# Stereo_RDS_Encoder-Analog_Board.net
KiCad netlist of a schematic drawn in EAGLE
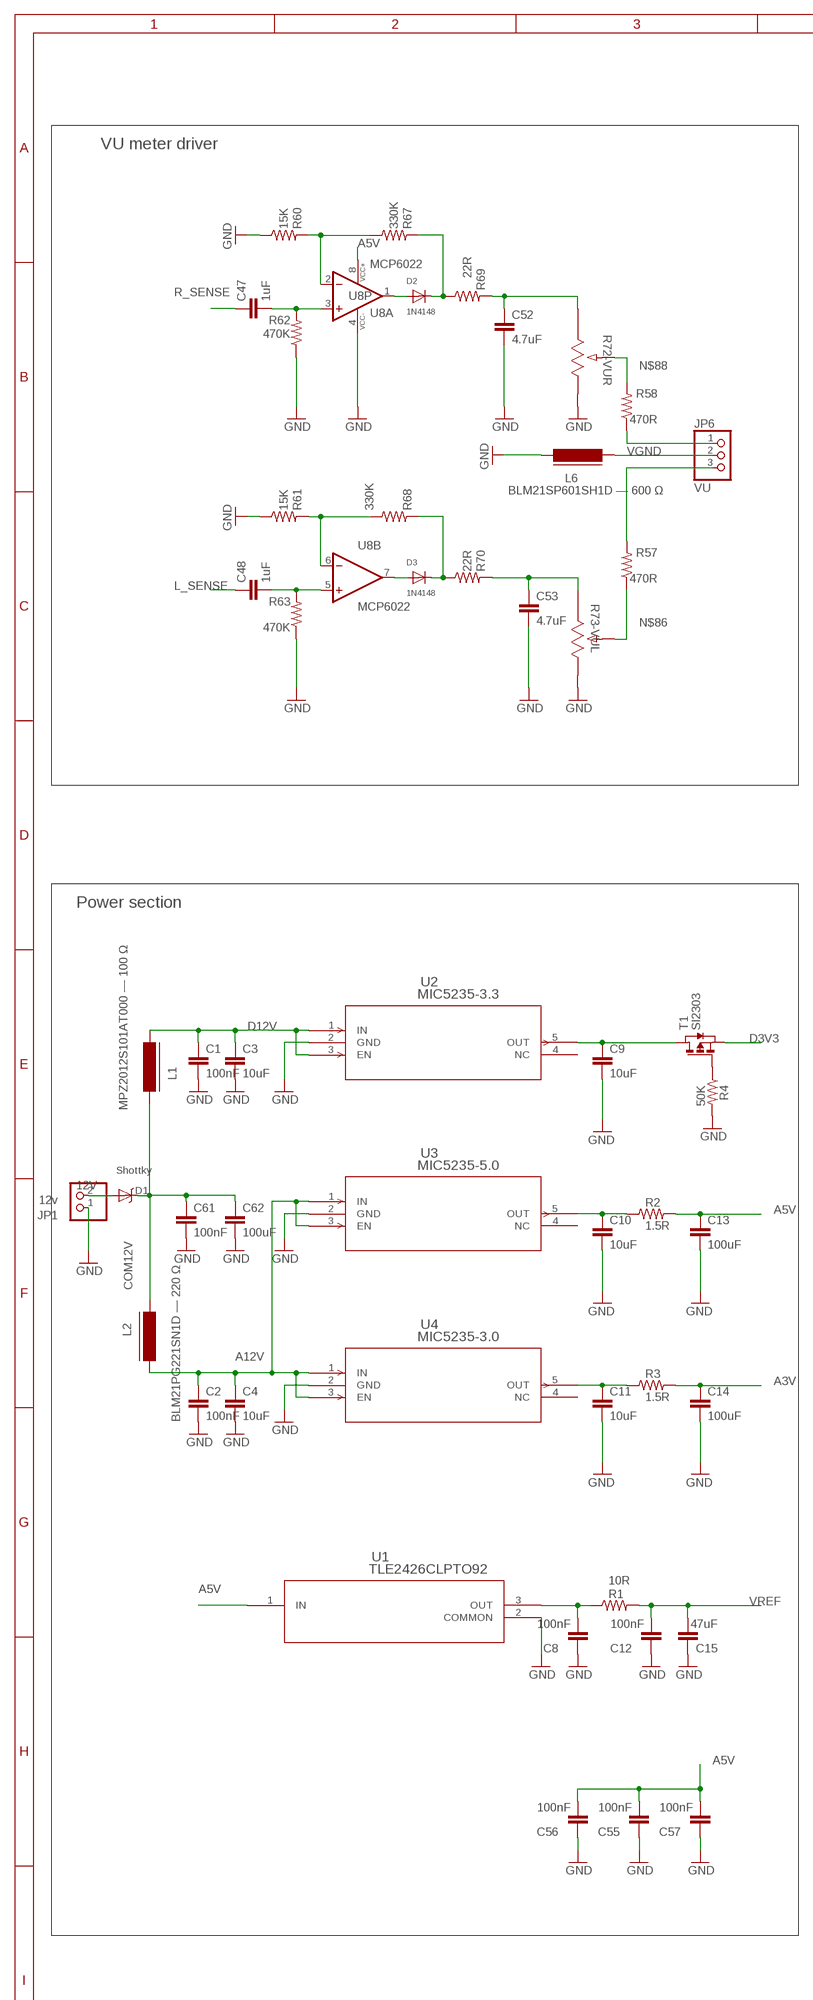
[diagram p0: schematic, sheet 1, part 1 of 2]
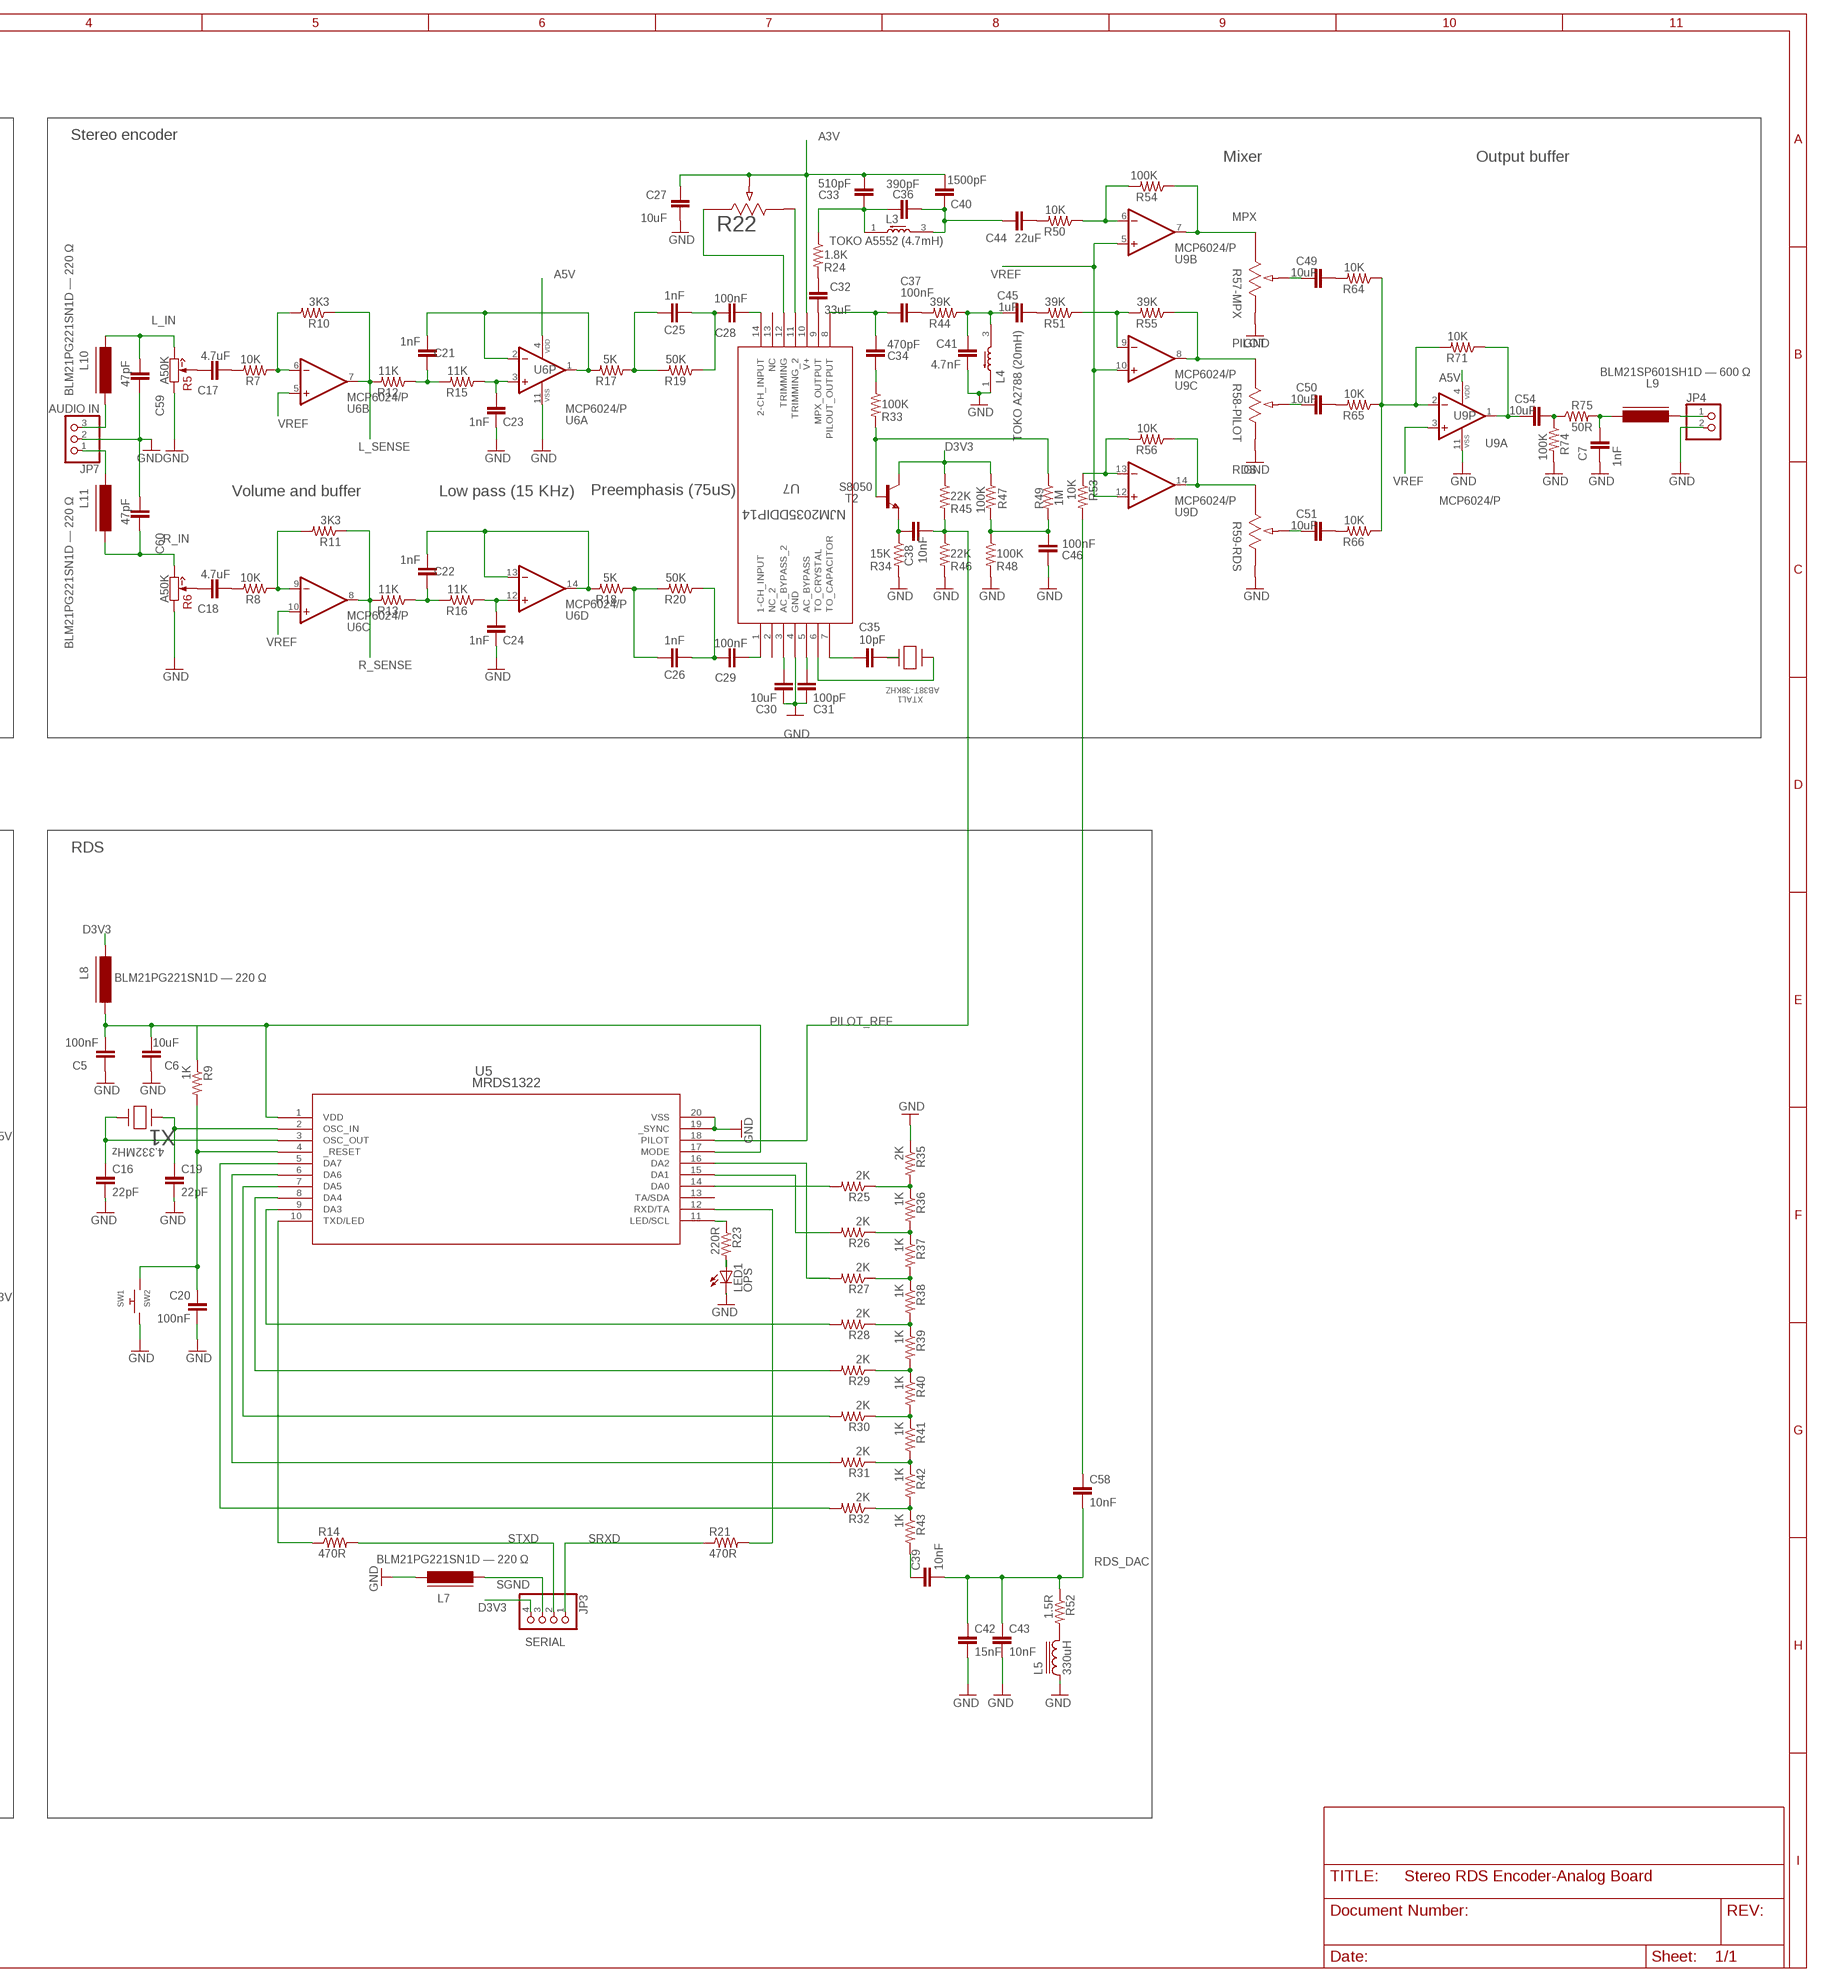
[diagram p1: schematic, sheet 1, part 2 of 2]

(export (version "E")
  (design (tool "Eeschema 10.0.6"))
  (components
    (comp (ref "C1")
      (value "100nF")
      (footprint "eagle-import:C0805")
      (libsource (lib "eagle-import") (part "C-EUC0805"))
    )
    (comp (ref "C2")
      (value "100nF")
      (footprint "eagle-import:C0805")
      (libsource (lib "eagle-import") (part "C-EUC0805"))
    )
    (comp (ref "C3")
      (value "10uF")
      (footprint "eagle-import:C0805")
      (libsource (lib "eagle-import") (part "C-EUC0805"))
    )
    (comp (ref "C4")
      (value "10uF")
      (footprint "eagle-import:C0805")
      (libsource (lib "eagle-import") (part "C-EUC0805"))
    )
    (comp (ref "C5")
      (value "100nF")
      (footprint "eagle-import:C0805")
      (libsource (lib "eagle-import") (part "C-EUC0805"))
    )
    (comp (ref "C6")
      (value "10uF")
      (footprint "eagle-import:C0805")
      (libsource (lib "eagle-import") (part "C-EUC0805"))
    )
    (comp (ref "C7")
      (value "1nF")
      (footprint "eagle-import:C0805")
      (libsource (lib "eagle-import") (part "C-EUC0805"))
    )
    (comp (ref "C8")
      (value "100nF")
      (footprint "eagle-import:C0805")
      (libsource (lib "eagle-import") (part "C-EUC0805"))
    )
    (comp (ref "C9")
      (value "10uF")
      (footprint "eagle-import:C0805")
      (libsource (lib "eagle-import") (part "C-EUC0805"))
    )
    (comp (ref "C10")
      (value "10uF")
      (footprint "eagle-import:C0805")
      (libsource (lib "eagle-import") (part "C-EUC0805"))
    )
    (comp (ref "C11")
      (value "10uF")
      (footprint "eagle-import:C0805")
      (libsource (lib "eagle-import") (part "C-EUC0805"))
    )
    (comp (ref "C12")
      (value "100nF")
      (footprint "eagle-import:C0805")
      (libsource (lib "eagle-import") (part "C-EUC0805"))
    )
    (comp (ref "C13")
      (value "100uF")
      (footprint "eagle-import:C0805")
      (libsource (lib "eagle-import") (part "C-EUC0805"))
    )
    (comp (ref "C14")
      (value "100uF")
      (footprint "eagle-import:C0805")
      (libsource (lib "eagle-import") (part "C-EUC0805"))
    )
    (comp (ref "C15")
      (value "47uF")
      (footprint "eagle-import:C0805")
      (libsource (lib "eagle-import") (part "C-EUC0805"))
    )
    (comp (ref "C16")
      (value "22pF")
      (footprint "eagle-import:C0805")
      (libsource (lib "eagle-import") (part "C-EUC0805"))
    )
    (comp (ref "C17")
      (value "4.7uF")
      (footprint "eagle-import:C0805")
      (libsource (lib "eagle-import") (part "C-EUC0805"))
    )
    (comp (ref "C18")
      (value "4.7uF")
      (footprint "eagle-import:C0805")
      (libsource (lib "eagle-import") (part "C-EUC0805"))
    )
    (comp (ref "C19")
      (value "22pF")
      (footprint "eagle-import:C0805")
      (libsource (lib "eagle-import") (part "C-EUC0805"))
    )
    (comp (ref "C20")
      (value "100nF")
      (footprint "eagle-import:C0805")
      (libsource (lib "eagle-import") (part "C-EUC0805"))
    )
    (comp (ref "C21")
      (value "1nF")
      (footprint "eagle-import:C0805")
      (libsource (lib "eagle-import") (part "C-EUC0805"))
    )
    (comp (ref "C22")
      (value "1nF")
      (footprint "eagle-import:C0805")
      (libsource (lib "eagle-import") (part "C-EUC0805"))
    )
    (comp (ref "C23")
      (value "1nF")
      (footprint "eagle-import:C0805")
      (libsource (lib "eagle-import") (part "C-EUC0805"))
    )
    (comp (ref "C24")
      (value "1nF")
      (footprint "eagle-import:C0805")
      (libsource (lib "eagle-import") (part "C-EUC0805"))
    )
    (comp (ref "C25")
      (value "1nF")
      (footprint "eagle-import:C0805")
      (libsource (lib "eagle-import") (part "C-EUC0805"))
    )
    (comp (ref "C26")
      (value "1nF")
      (footprint "eagle-import:C0805")
      (libsource (lib "eagle-import") (part "C-EUC0805"))
    )
    (comp (ref "C27")
      (value "10uF")
      (footprint "eagle-import:C0805")
      (libsource (lib "eagle-import") (part "C-EUC0805"))
    )
    (comp (ref "C28")
      (value "100nF")
      (footprint "eagle-import:C0805")
      (libsource (lib "eagle-import") (part "C-EUC0805"))
    )
    (comp (ref "C29")
      (value "100nF")
      (footprint "eagle-import:C0805")
      (libsource (lib "eagle-import") (part "C-EUC0805"))
    )
    (comp (ref "C30")
      (value "10uF")
      (footprint "eagle-import:C0805")
      (libsource (lib "eagle-import") (part "C-EUC0805"))
    )
    (comp (ref "C31")
      (value "100pF")
      (footprint "eagle-import:C0805")
      (libsource (lib "eagle-import") (part "C-EUC0805"))
    )
    (comp (ref "C32")
      (value "33uF")
      (footprint "eagle-import:C0805")
      (libsource (lib "eagle-import") (part "C-EUC0805"))
    )
    (comp (ref "C33")
      (value "510pF")
      (footprint "eagle-import:C0805")
      (libsource (lib "eagle-import") (part "C-EUC0805"))
    )
    (comp (ref "C34")
      (value "470pF")
      (footprint "eagle-import:C0805")
      (libsource (lib "eagle-import") (part "C-EUC0805"))
    )
    (comp (ref "C35")
      (value "10pF")
      (footprint "eagle-import:C0805")
      (libsource (lib "eagle-import") (part "C-EUC0805"))
    )
    (comp (ref "C36")
      (value "390pF")
      (footprint "eagle-import:C0805")
      (libsource (lib "eagle-import") (part "C-EUC0805"))
    )
    (comp (ref "C37")
      (value "100nF")
      (footprint "eagle-import:C0805")
      (libsource (lib "eagle-import") (part "C-EUC0805"))
    )
    (comp (ref "C38")
      (value "10nF")
      (footprint "eagle-import:C0805")
      (libsource (lib "eagle-import") (part "C-EUC0805"))
    )
    (comp (ref "C39")
      (value "10nF")
      (footprint "eagle-import:C0805")
      (libsource (lib "eagle-import") (part "C-EUC0805"))
    )
    (comp (ref "C40")
      (value "1500pF")
      (footprint "eagle-import:C0805")
      (libsource (lib "eagle-import") (part "C-EUC0805"))
    )
    (comp (ref "C41")
      (value "4.7nF")
      (footprint "eagle-import:C0805")
      (libsource (lib "eagle-import") (part "C-EUC0805"))
    )
    (comp (ref "C42")
      (value "15nF")
      (footprint "eagle-import:C0805")
      (libsource (lib "eagle-import") (part "C-EUC0805"))
    )
    (comp (ref "C43")
      (value "10nF")
      (footprint "eagle-import:C0805")
      (libsource (lib "eagle-import") (part "C-EUC0805"))
    )
    (comp (ref "C44")
      (value "22uF")
      (footprint "eagle-import:C0805")
      (libsource (lib "eagle-import") (part "C-EUC0805"))
    )
    (comp (ref "C45")
      (value "1uF")
      (footprint "eagle-import:C0805")
      (libsource (lib "eagle-import") (part "C-EUC0805"))
    )
    (comp (ref "C46")
      (value "100nF")
      (footprint "eagle-import:C0805")
      (libsource (lib "eagle-import") (part "C-EUC0805"))
    )
    (comp (ref "C47")
      (value "1uF")
      (footprint "eagle-import:C0805")
      (libsource (lib "eagle-import") (part "C-EUC0805"))
    )
    (comp (ref "C48")
      (value "1uF")
      (footprint "eagle-import:C0805")
      (libsource (lib "eagle-import") (part "C-EUC0805"))
    )
    (comp (ref "C49")
      (value "10uF")
      (footprint "eagle-import:C0805")
      (libsource (lib "eagle-import") (part "C-EUC0805"))
    )
    (comp (ref "C50")
      (value "10uF")
      (footprint "eagle-import:C0805")
      (libsource (lib "eagle-import") (part "C-EUC0805"))
    )
    (comp (ref "C51")
      (value "10uF")
      (footprint "eagle-import:C0805")
      (libsource (lib "eagle-import") (part "C-EUC0805"))
    )
    (comp (ref "C52")
      (value "4.7uF")
      (footprint "eagle-import:C0805")
      (libsource (lib "eagle-import") (part "C-EUC0805"))
    )
    (comp (ref "C53")
      (value "4.7uF")
      (footprint "eagle-import:C0805")
      (libsource (lib "eagle-import") (part "C-EUC0805"))
    )
    (comp (ref "C54")
      (value "10uF")
      (footprint "eagle-import:C0805")
      (libsource (lib "eagle-import") (part "C-EUC0805"))
    )
    (comp (ref "C55")
      (value "100nF")
      (footprint "eagle-import:C0805")
      (libsource (lib "eagle-import") (part "C-EUC0805"))
    )
    (comp (ref "C56")
      (value "100nF")
      (footprint "eagle-import:C0805")
      (libsource (lib "eagle-import") (part "C-EUC0805"))
    )
    (comp (ref "C57")
      (value "100nF")
      (footprint "eagle-import:C0805")
      (libsource (lib "eagle-import") (part "C-EUC0805"))
    )
    (comp (ref "C58")
      (value "10nF")
      (footprint "eagle-import:C0805")
      (libsource (lib "eagle-import") (part "C-EUC0805"))
    )
    (comp (ref "C59")
      (value "47pF")
      (footprint "eagle-import:C0805")
      (libsource (lib "eagle-import") (part "C-EUC0805"))
    )
    (comp (ref "C60")
      (value "47pF")
      (footprint "eagle-import:C0805")
      (libsource (lib "eagle-import") (part "C-EUC0805"))
    )
    (comp (ref "C61")
      (value "100nF")
      (footprint "eagle-import:C0805")
      (libsource (lib "eagle-import") (part "C-EUC0805"))
    )
    (comp (ref "C62")
      (value "100uF")
      (footprint "eagle-import:C0805")
      (libsource (lib "eagle-import") (part "C-EUC0805"))
    )
    (comp (ref "D1")
      (value "Shottky")
      (footprint "eagle-import:SMA-403D")
      (libsource (lib "eagle-import") (part "DIODE-SCHOTTKYSMA-403D"))
    )
    (comp (ref "D2")
      (value "1N4148")
      (footprint "eagle-import:SOD-323F")
      (libsource (lib "eagle-import") (part "DIODESOD-323F"))
    )
    (comp (ref "D3")
      (value "1N4148")
      (footprint "eagle-import:SOD-323F")
      (libsource (lib "eagle-import") (part "DIODESOD-323F"))
    )
    (comp (ref "JP1")
      (value "12v")
      (footprint "eagle-import:1X02")
      (libsource (lib "eagle-import") (part "PINHD-1X2"))
    )
    (comp (ref "JP3")
      (value "SERIAL")
      (footprint "eagle-import:1X04")
      (libsource (lib "eagle-import") (part "PINHD-1X4"))
    )
    (comp (ref "JP4")
      (value "PINHD-1X2")
      (footprint "eagle-import:1X02")
      (libsource (lib "eagle-import") (part "PINHD-1X2"))
    )
    (comp (ref "JP6")
      (value "VU")
      (footprint "eagle-import:1X03")
      (libsource (lib "eagle-import") (part "PINHD-1X3"))
    )
    (comp (ref "JP7")
      (value "AUDIO IN")
      (footprint "eagle-import:1X03")
      (libsource (lib "eagle-import") (part "PINHD-1X3"))
    )
    (comp (ref "L1")
      (value "MPZ2012S101AT000 — 100 Ω")
      (footprint "eagle-import:FB805")
      (libsource (lib "eagle-import") (part "FERRITE-0805"))
    )
    (comp (ref "L2")
      (value "BLM21PG221SN1D — 220 Ω")
      (footprint "eagle-import:FB805")
      (libsource (lib "eagle-import") (part "FERRITE-0805"))
    )
    (comp (ref "L3")
      (value "TOKO A5552 (4.7mH)")
      (footprint "eagle-import:7KMM")
      (libsource (lib "eagle-import") (part "7KMM"))
    )
    (comp (ref "L4")
      (value "TOKO A2788 (20mH)")
      (footprint "eagle-import:7KMM")
      (libsource (lib "eagle-import") (part "7KMM"))
    )
    (comp (ref "L5")
      (value "330uH")
      (footprint "eagle-import:8RB")
      (libsource (lib "eagle-import") (part "8RB"))
    )
    (comp (ref "L6")
      (value "BLM21SP601SH1D — 600 Ω")
      (footprint "eagle-import:FB805")
      (libsource (lib "eagle-import") (part "FERRITE-0805"))
    )
    (comp (ref "L7")
      (value "BLM21PG221SN1D — 220 Ω")
      (footprint "eagle-import:FB805")
      (libsource (lib "eagle-import") (part "FERRITE-0805"))
    )
    (comp (ref "L8")
      (value "BLM21PG221SN1D — 220 Ω")
      (footprint "eagle-import:FB805")
      (libsource (lib "eagle-import") (part "FERRITE-0805"))
    )
    (comp (ref "L9")
      (value "BLM21SP601SH1D — 600 Ω")
      (footprint "eagle-import:FB805")
      (libsource (lib "eagle-import") (part "FERRITE-0805"))
    )
    (comp (ref "L10")
      (value "BLM21PG221SN1D — 220 Ω")
      (footprint "eagle-import:FB805")
      (libsource (lib "eagle-import") (part "FERRITE-0805"))
    )
    (comp (ref "L11")
      (value "BLM21PG221SN1D — 220 Ω")
      (footprint "eagle-import:FB805")
      (libsource (lib "eagle-import") (part "FERRITE-0805"))
    )
    (comp (ref "LED1")
      (value "OPS")
      (footprint "eagle-import:CHIPLED_0805")
      (libsource (lib "eagle-import") (part "LEDCHIPLED_0805"))
    )
    (comp (ref "R1")
      (value "10R")
      (footprint "eagle-import:M0805")
      (libsource (lib "eagle-import") (part "R-US_M0805"))
    )
    (comp (ref "R2")
      (value "1.5R")
      (footprint "eagle-import:M0805")
      (libsource (lib "eagle-import") (part "R-US_M0805"))
    )
    (comp (ref "R3")
      (value "1.5R")
      (footprint "eagle-import:M0805")
      (libsource (lib "eagle-import") (part "R-US_M0805"))
    )
    (comp (ref "R4")
      (value "50K")
      (footprint "eagle-import:M0805")
      (libsource (lib "eagle-import") (part "R-US_M0805"))
    )
    (comp (ref "R5")
      (value "A50K")
      (footprint "eagle-import:RV09-SINGLE")
      (libsource (lib "eagle-import") (part "?A10K(9MM)"))
    )
    (comp (ref "R6")
      (value "A50K")
      (footprint "eagle-import:RV09-SINGLE")
      (libsource (lib "eagle-import") (part "?A10K(9MM)"))
    )
    (comp (ref "R7")
      (value "10K")
      (footprint "eagle-import:M0805")
      (libsource (lib "eagle-import") (part "R-US_M0805"))
    )
    (comp (ref "R8")
      (value "10K")
      (footprint "eagle-import:M0805")
      (libsource (lib "eagle-import") (part "R-US_M0805"))
    )
    (comp (ref "R9")
      (value "1K")
      (footprint "eagle-import:M0805")
      (libsource (lib "eagle-import") (part "R-US_M0805"))
    )
    (comp (ref "R10")
      (value "3K3")
      (footprint "eagle-import:M0805")
      (libsource (lib "eagle-import") (part "R-US_M0805"))
    )
    (comp (ref "R11")
      (value "3K3")
      (footprint "eagle-import:M0805")
      (libsource (lib "eagle-import") (part "R-US_M0805"))
    )
    (comp (ref "R12")
      (value "11K")
      (footprint "eagle-import:M0805")
      (libsource (lib "eagle-import") (part "R-US_M0805"))
    )
    (comp (ref "R13")
      (value "11K")
      (footprint "eagle-import:M0805")
      (libsource (lib "eagle-import") (part "R-US_M0805"))
    )
    (comp (ref "R14")
      (value "470R")
      (footprint "eagle-import:M0805")
      (libsource (lib "eagle-import") (part "R-US_M0805"))
    )
    (comp (ref "R15")
      (value "11K")
      (footprint "eagle-import:M0805")
      (libsource (lib "eagle-import") (part "R-US_M0805"))
    )
    (comp (ref "R16")
      (value "11K")
      (footprint "eagle-import:M0805")
      (libsource (lib "eagle-import") (part "R-US_M0805"))
    )
    (comp (ref "R17")
      (value "5K")
      (footprint "eagle-import:M0805")
      (libsource (lib "eagle-import") (part "R-US_M0805"))
    )
    (comp (ref "R18")
      (value "5K")
      (footprint "eagle-import:M0805")
      (libsource (lib "eagle-import") (part "R-US_M0805"))
    )
    (comp (ref "R19")
      (value "50K")
      (footprint "eagle-import:M0805")
      (libsource (lib "eagle-import") (part "R-US_M0805"))
    )
    (comp (ref "R20")
      (value "50K")
      (footprint "eagle-import:M0805")
      (libsource (lib "eagle-import") (part "R-US_M0805"))
    )
    (comp (ref "R21")
      (value "470R")
      (footprint "eagle-import:M0805")
      (libsource (lib "eagle-import") (part "R-US_M0805"))
    )
    (comp (ref "R22")
      (value "50K")
      (footprint "eagle-import:POT_3296W")
      (fields
        (field (name "MANUFACTURER_PART_NUMBER") "3296W-1-503LF")
        (field (name "COPYRIGHT") "Copyright (C) 2025 Ultra Librarian. All rights reserved.")
      )
      (libsource (lib "eagle-import") (part "3296W-1-503LF"))
    )
    (comp (ref "R23")
      (value "220R")
      (footprint "eagle-import:M0805")
      (libsource (lib "eagle-import") (part "R-US_M0805"))
    )
    (comp (ref "R24")
      (value "1.8K")
      (footprint "eagle-import:M0805")
      (libsource (lib "eagle-import") (part "R-US_M0805"))
    )
    (comp (ref "R25")
      (value "2K")
      (footprint "eagle-import:M0805")
      (libsource (lib "eagle-import") (part "R-US_M0805"))
    )
    (comp (ref "R26")
      (value "2K")
      (footprint "eagle-import:M0805")
      (libsource (lib "eagle-import") (part "R-US_M0805"))
    )
    (comp (ref "R27")
      (value "2K")
      (footprint "eagle-import:M0805")
      (libsource (lib "eagle-import") (part "R-US_M0805"))
    )
    (comp (ref "R28")
      (value "2K")
      (footprint "eagle-import:M0805")
      (libsource (lib "eagle-import") (part "R-US_M0805"))
    )
    (comp (ref "R29")
      (value "2K")
      (footprint "eagle-import:M0805")
      (libsource (lib "eagle-import") (part "R-US_M0805"))
    )
    (comp (ref "R30")
      (value "2K")
      (footprint "eagle-import:M0805")
      (libsource (lib "eagle-import") (part "R-US_M0805"))
    )
    (comp (ref "R31")
      (value "2K")
      (footprint "eagle-import:M0805")
      (libsource (lib "eagle-import") (part "R-US_M0805"))
    )
    (comp (ref "R32")
      (value "2K")
      (footprint "eagle-import:M0805")
      (libsource (lib "eagle-import") (part "R-US_M0805"))
    )
    (comp (ref "R33")
      (value "100K")
      (footprint "eagle-import:M0805")
      (libsource (lib "eagle-import") (part "R-US_M0805"))
    )
    (comp (ref "R34")
      (value "15K")
      (footprint "eagle-import:M0805")
      (libsource (lib "eagle-import") (part "R-US_M0805"))
    )
    (comp (ref "R35")
      (value "2K")
      (footprint "eagle-import:M0805")
      (libsource (lib "eagle-import") (part "R-US_M0805"))
    )
    (comp (ref "R36")
      (value "1K")
      (footprint "eagle-import:M0805")
      (libsource (lib "eagle-import") (part "R-US_M0805"))
    )
    (comp (ref "R37")
      (value "1K")
      (footprint "eagle-import:M0805")
      (libsource (lib "eagle-import") (part "R-US_M0805"))
    )
    (comp (ref "R38")
      (value "1K")
      (footprint "eagle-import:M0805")
      (libsource (lib "eagle-import") (part "R-US_M0805"))
    )
    (comp (ref "R39")
      (value "1K")
      (footprint "eagle-import:M0805")
      (libsource (lib "eagle-import") (part "R-US_M0805"))
    )
    (comp (ref "R40")
      (value "1K")
      (footprint "eagle-import:M0805")
      (libsource (lib "eagle-import") (part "R-US_M0805"))
    )
    (comp (ref "R41")
      (value "1K")
      (footprint "eagle-import:M0805")
      (libsource (lib "eagle-import") (part "R-US_M0805"))
    )
    (comp (ref "R42")
      (value "1K")
      (footprint "eagle-import:M0805")
      (libsource (lib "eagle-import") (part "R-US_M0805"))
    )
    (comp (ref "R43")
      (value "1K")
      (footprint "eagle-import:M0805")
      (libsource (lib "eagle-import") (part "R-US_M0805"))
    )
    (comp (ref "R44")
      (value "39K")
      (footprint "eagle-import:M0805")
      (libsource (lib "eagle-import") (part "R-US_M0805"))
    )
    (comp (ref "R45")
      (value "22K")
      (footprint "eagle-import:M0805")
      (libsource (lib "eagle-import") (part "R-US_M0805"))
    )
    (comp (ref "R46")
      (value "22K")
      (footprint "eagle-import:M0805")
      (libsource (lib "eagle-import") (part "R-US_M0805"))
    )
    (comp (ref "R47")
      (value "100K")
      (footprint "eagle-import:M0805")
      (libsource (lib "eagle-import") (part "R-US_M0805"))
    )
    (comp (ref "R48")
      (value "100K")
      (footprint "eagle-import:M0805")
      (libsource (lib "eagle-import") (part "R-US_M0805"))
    )
    (comp (ref "R49")
      (value "1M")
      (footprint "eagle-import:M0805")
      (libsource (lib "eagle-import") (part "R-US_M0805"))
    )
    (comp (ref "R50")
      (value "10K")
      (footprint "eagle-import:M0805")
      (libsource (lib "eagle-import") (part "R-US_M0805"))
    )
    (comp (ref "R51")
      (value "39K")
      (footprint "eagle-import:M0805")
      (libsource (lib "eagle-import") (part "R-US_M0805"))
    )
    (comp (ref "R52")
      (value "1.5R")
      (footprint "eagle-import:M0805")
      (libsource (lib "eagle-import") (part "R-US_M0805"))
    )
    (comp (ref "R53")
      (value "10K")
      (footprint "eagle-import:M0805")
      (libsource (lib "eagle-import") (part "R-US_M0805"))
    )
    (comp (ref "R54")
      (value "100K")
      (footprint "eagle-import:M0805")
      (libsource (lib "eagle-import") (part "R-US_M0805"))
    )
    (comp (ref "R55")
      (value "39K")
      (footprint "eagle-import:M0805")
      (libsource (lib "eagle-import") (part "R-US_M0805"))
    )
    (comp (ref "R56")
      (value "10K")
      (footprint "eagle-import:M0805")
      (libsource (lib "eagle-import") (part "R-US_M0805"))
    )
    (comp (ref "R57")
      (value "470R")
      (footprint "eagle-import:M0805")
      (libsource (lib "eagle-import") (part "R-US_M0805"))
    )
    (comp (ref "R57-MPX")
      (value "50K")
      (footprint "eagle-import:POT_3296W")
      (fields
        (field (name "MANUFACTURER_PART_NUMBER") "3296W-1-503LF")
        (field (name "COPYRIGHT") "Copyright (C) 2025 Ultra Librarian. All rights reserved.")
      )
      (libsource (lib "eagle-import") (part "3296W-1-503LF"))
    )
    (comp (ref "R58")
      (value "470R")
      (footprint "eagle-import:M0805")
      (libsource (lib "eagle-import") (part "R-US_M0805"))
    )
    (comp (ref "R58-PILOT")
      (value "50K")
      (footprint "eagle-import:POT_3296W")
      (fields
        (field (name "MANUFACTURER_PART_NUMBER") "3296W-1-503LF")
        (field (name "COPYRIGHT") "Copyright (C) 2025 Ultra Librarian. All rights reserved.")
      )
      (libsource (lib "eagle-import") (part "3296W-1-503LF"))
    )
    (comp (ref "R59-RDS")
      (value "50K")
      (footprint "eagle-import:POT_3296W")
      (fields
        (field (name "MANUFACTURER_PART_NUMBER") "3296W-1-503LF")
        (field (name "COPYRIGHT") "Copyright (C) 2025 Ultra Librarian. All rights reserved.")
      )
      (libsource (lib "eagle-import") (part "3296W-1-503LF"))
    )
    (comp (ref "R60")
      (value "15K")
      (footprint "eagle-import:M0805")
      (libsource (lib "eagle-import") (part "R-US_M0805"))
    )
    (comp (ref "R61")
      (value "15K")
      (footprint "eagle-import:M0805")
      (libsource (lib "eagle-import") (part "R-US_M0805"))
    )
    (comp (ref "R62")
      (value "470K")
      (footprint "eagle-import:M0805")
      (libsource (lib "eagle-import") (part "R-US_M0805"))
    )
    (comp (ref "R63")
      (value "470K")
      (footprint "eagle-import:M0805")
      (libsource (lib "eagle-import") (part "R-US_M0805"))
    )
    (comp (ref "R64")
      (value "10K")
      (footprint "eagle-import:M0805")
      (libsource (lib "eagle-import") (part "R-US_M0805"))
    )
    (comp (ref "R65")
      (value "10K")
      (footprint "eagle-import:M0805")
      (libsource (lib "eagle-import") (part "R-US_M0805"))
    )
    (comp (ref "R66")
      (value "10K")
      (footprint "eagle-import:M0805")
      (libsource (lib "eagle-import") (part "R-US_M0805"))
    )
    (comp (ref "R67")
      (value "330K")
      (footprint "eagle-import:M0805")
      (libsource (lib "eagle-import") (part "R-US_M0805"))
    )
    (comp (ref "R68")
      (value "330K")
      (footprint "eagle-import:M0805")
      (libsource (lib "eagle-import") (part "R-US_M0805"))
    )
    (comp (ref "R69")
      (value "22R")
      (footprint "eagle-import:M0805")
      (libsource (lib "eagle-import") (part "R-US_M0805"))
    )
    (comp (ref "R70")
      (value "22R")
      (footprint "eagle-import:M0805")
      (libsource (lib "eagle-import") (part "R-US_M0805"))
    )
    (comp (ref "R71")
      (value "10K")
      (footprint "eagle-import:M0805")
      (libsource (lib "eagle-import") (part "R-US_M0805"))
    )
    (comp (ref "R72-VUR")
      (value "50K")
      (footprint "eagle-import:POT_3296W")
      (fields
        (field (name "MANUFACTURER_PART_NUMBER") "3296W-1-503LF")
        (field (name "COPYRIGHT") "Copyright (C) 2025 Ultra Librarian. All rights reserved.")
      )
      (libsource (lib "eagle-import") (part "3296W-1-503LF"))
    )
    (comp (ref "R73-VUL")
      (value "50K")
      (footprint "eagle-import:POT_3296W")
      (fields
        (field (name "MANUFACTURER_PART_NUMBER") "3296W-1-503LF")
        (field (name "COPYRIGHT") "Copyright (C) 2025 Ultra Librarian. All rights reserved.")
      )
      (libsource (lib "eagle-import") (part "3296W-1-503LF"))
    )
    (comp (ref "R74")
      (value "100K")
      (footprint "eagle-import:M0805")
      (libsource (lib "eagle-import") (part "R-US_M0805"))
    )
    (comp (ref "R75")
      (value "50R")
      (footprint "eagle-import:M0805")
      (libsource (lib "eagle-import") (part "R-US_M0805"))
    )
    (comp (ref "SW1")
      (value "SW2")
      (footprint "eagle-import:BTN_CK_KSS")
      (libsource (lib "eagle-import") (part "SWITCH_PUSHBUTTONC&K_KSS"))
    )
    (comp (ref "T1")
      (value "SI2303")
      (footprint "eagle-import:SOT-23")
      (libsource (lib "eagle-import") (part "PMOSSOT23"))
    )
    (comp (ref "T2")
      (value "S8050")
      (footprint "eagle-import:SOT23")
      (libsource (lib "eagle-import") (part "BC846"))
    )
    (comp (ref "U1")
      (value "TLE2426CLPTO92")
      (footprint "eagle-import:TO92")
      (libsource (lib "eagle-import") (part "TLE2426CLPTO92"))
    )
    (comp (ref "U2")
      (value "MIC5235-3.3")
      (footprint "eagle-import:SOT-23-5_M5_MCH-M")
      (fields
        (field (name "MANUFACTURER_PART_NUMBER") "MIC5235-1.8YM5-TR")
        (field (name "COPYRIGHT") "Copyright (C) 2025 Ultra Librarian. All rights reserved.")
      )
      (libsource (lib "eagle-import") (part "MIC5235-1.8YM5-TRSOT-23-5_M5_MCH-M"))
    )
    (comp (ref "U3")
      (value "MIC5235-5.0")
      (footprint "eagle-import:SOT-23-5_M5_MCH-M")
      (fields
        (field (name "MANUFACTURER_PART_NUMBER") "MIC5235-1.8YM5-TR")
        (field (name "COPYRIGHT") "Copyright (C) 2025 Ultra Librarian. All rights reserved.")
      )
      (libsource (lib "eagle-import") (part "MIC5235-1.8YM5-TRSOT-23-5_M5_MCH-M"))
    )
    (comp (ref "U4")
      (value "MIC5235-3.0")
      (footprint "eagle-import:SOT-23-5_M5_MCH-M")
      (fields
        (field (name "MANUFACTURER_PART_NUMBER") "MIC5235-1.8YM5-TR")
        (field (name "COPYRIGHT") "Copyright (C) 2025 Ultra Librarian. All rights reserved.")
      )
      (libsource (lib "eagle-import") (part "MIC5235-1.8YM5-TRSOT-23-5_M5_MCH-M"))
    )
    (comp (ref "U5")
      (value "MRDS1322")
      (footprint "eagle-import:PDIP20_300MC_MCH")
      (fields
        (field (name "MANUFACTURER_PART_NUMBER") "PIC16F1509-E/P")
        (field (name "COPYRIGHT") "Copyright (C) 2025 Ultra Librarian. All rights reserved.")
      )
      (libsource (lib "eagle-import") (part "MRDS1322"))
    )
    (comp (ref "U6")
      (value "MCP6024/P")
      (footprint "eagle-import:DIL14")
      (libsource (lib "eagle-import") (part "MCP6024/P"))
    )
    (comp (ref "U7")
      (value "NJM2035DDIP14")
      (footprint "eagle-import:DIP14")
      (libsource (lib "eagle-import") (part "NJM2035DDIP14"))
    )
    (comp (ref "U8")
      (value "MCP6022")
      (footprint "eagle-import:DIL08")
      (libsource (lib "eagle-import") (part "TL072P"))
    )
    (comp (ref "U9")
      (value "MCP6024/P")
      (footprint "eagle-import:DIL14")
      (libsource (lib "eagle-import") (part "MCP6024/P"))
    )
    (comp (ref "X1")
      (value "4.332MHz")
      (footprint "eagle-import:XTAL_HC-49_U-S_CFC")
      (fields
        (field (name "MANUFACTURER_PART_NUMBER") "HC-49/U-S15000000ABJB")
        (field (name "COPYRIGHT") "Copyright (C) 2025 Ultra Librarian. All rights reserved.")
      )
      (libsource (lib "eagle-import") (part "HC-49/U-S15000000ABJB"))
    )
    (comp (ref "XTAL1")
      (value "AB38T-38KHZ")
      (footprint "eagle-import:XTAL_AB38T_ABR")
      (fields
        (field (name "MANUFACTURER_PART_NUMBER") "AB38T-32.768KHZ")
        (field (name "COPYRIGHT") "Copyright (C) 2025 Ultra Librarian. All rights reserved.")
      )
      (libsource (lib "eagle-import") (part "AB38T-32.768KHZ"))
    )
  )
  (nets
    (net (code "1") (name "/12V") (class "Default")
      (node (ref "D1") (pin "A") (pinfunction "A_A") (pintype "passive"))
      (node (ref "JP1") (pin "2") (pinfunction "2_2") (pintype "passive"))
    )
    (net (code "2") (name "/A3V") (class "Default")
      (node (ref "C14") (pin "1") (pinfunction "1_1") (pintype "passive"))
      (node (ref "C27") (pin "1") (pinfunction "1_1") (pintype "passive"))
      (node (ref "C33") (pin "1") (pinfunction "1_1") (pintype "passive"))
      (node (ref "C40") (pin "1") (pinfunction "1_1") (pintype "passive"))
      (node (ref "R22") (pin "2") (pinfunction "2_2") (pintype "passive"))
      (node (ref "R3") (pin "2") (pinfunction "2_2") (pintype "passive"))
      (node (ref "U7") (pin "10") (pinfunction "V+_10") (pintype "power_in"))
    )
    (net (code "3") (name "/A5V") (class "Default")
      (node (ref "C13") (pin "1") (pinfunction "1_1") (pintype "passive"))
      (node (ref "C55") (pin "2") (pinfunction "2_2") (pintype "passive"))
      (node (ref "C56") (pin "2") (pinfunction "2_2") (pintype "passive"))
      (node (ref "C57") (pin "2") (pinfunction "2_2") (pintype "passive"))
      (node (ref "R2") (pin "2") (pinfunction "2_2") (pintype "passive"))
      (node (ref "U1") (pin "1") (pinfunction "IN_1") (pintype "input"))
      (node (ref "U6") (pin "4") (pinfunction "VDD_4") (pintype "power_in"))
      (node (ref "U8") (pin "8") (pinfunction "VCC+_8") (pintype "power_in"))
      (node (ref "U9") (pin "4") (pinfunction "VDD_4") (pintype "power_in"))
    )
    (net (code "4") (name "/A12V") (class "Default")
      (node (ref "C2") (pin "1") (pinfunction "1_1") (pintype "passive"))
      (node (ref "C4") (pin "1") (pinfunction "1_1") (pintype "passive"))
      (node (ref "L2") (pin "2") (pinfunction "2_2") (pintype "passive"))
      (node (ref "U3") (pin "1") (pinfunction "IN_1") (pintype "input"))
      (node (ref "U3") (pin "3") (pinfunction "EN_3") (pintype "input"))
      (node (ref "U4") (pin "1") (pinfunction "IN_1") (pintype "input"))
      (node (ref "U4") (pin "3") (pinfunction "EN_3") (pintype "input"))
    )
    (net (code "5") (name "/COM12V") (class "Default")
      (node (ref "C61") (pin "1") (pinfunction "1_1") (pintype "passive"))
      (node (ref "C62") (pin "1") (pinfunction "1_1") (pintype "passive"))
      (node (ref "D1") (pin "C") (pinfunction "C_C") (pintype "passive"))
      (node (ref "L1") (pin "1") (pinfunction "1_1") (pintype "passive"))
      (node (ref "L2") (pin "1") (pinfunction "1_1") (pintype "passive"))
    )
    (net (code "6") (name "/D3V3") (class "Default")
      (node (ref "JP3") (pin "4") (pinfunction "4_4") (pintype "passive"))
      (node (ref "L8") (pin "1") (pinfunction "1_1") (pintype "passive"))
      (node (ref "R45") (pin "1") (pinfunction "1_1") (pintype "passive"))
      (node (ref "R47") (pin "1") (pinfunction "1_1") (pintype "passive"))
      (node (ref "T1") (pin "2") (pinfunction "S_2") (pintype "passive"))
      (node (ref "T2") (pin "3") (pinfunction "C_3") (pintype "passive"))
    )
    (net (code "7") (name "/D12V") (class "Default")
      (node (ref "C1") (pin "1") (pinfunction "1_1") (pintype "passive"))
      (node (ref "C3") (pin "1") (pinfunction "1_1") (pintype "passive"))
      (node (ref "L1") (pin "2") (pinfunction "2_2") (pintype "passive"))
      (node (ref "U2") (pin "1") (pinfunction "IN_1") (pintype "input"))
      (node (ref "U2") (pin "3") (pinfunction "EN_3") (pintype "input"))
    )
    (net (code "8") (name "/L_IN") (class "Default")
      (node (ref "C59") (pin "2") (pinfunction "2_2") (pintype "passive"))
      (node (ref "L10") (pin "1") (pinfunction "1_1") (pintype "passive"))
      (node (ref "R5") (pin "3") (pinfunction "CW_3") (pintype "passive"))
    )
    (net (code "9") (name "/L_SENSE") (class "Default")
      (node (ref "C48") (pin "1") (pinfunction "1_1") (pintype "passive"))
      (node (ref "R10") (pin "1") (pinfunction "1_1") (pintype "passive"))
      (node (ref "R12") (pin "2") (pinfunction "2_2") (pintype "passive"))
      (node (ref "U6") (pin "7") (pinfunction "OUT_7") (pintype "output"))
    )
    (net (code "10") (name "/MPX") (class "Default")
      (node (ref "R54") (pin "1") (pinfunction "1_1") (pintype "passive"))
      (node (ref "R57-MPX") (pin "1") (pinfunction "1_1") (pintype "passive"))
      (node (ref "U9") (pin "7") (pinfunction "OUT_7") (pintype "output"))
    )
    (net (code "11") (name "/N$86") (class "Default")
      (node (ref "R57") (pin "1") (pinfunction "1_1") (pintype "passive"))
      (node (ref "R73-VUL") (pin "2") (pinfunction "2_2") (pintype "passive"))
    )
    (net (code "12") (name "/N$88") (class "Default")
      (node (ref "R58") (pin "2") (pinfunction "2_2") (pintype "passive"))
      (node (ref "R72-VUR") (pin "2") (pinfunction "2_2") (pintype "passive"))
    )
    (net (code "13") (name "/PILOT") (class "Default")
      (node (ref "R55") (pin "1") (pinfunction "1_1") (pintype "passive"))
      (node (ref "R58-PILOT") (pin "1") (pinfunction "1_1") (pintype "passive"))
      (node (ref "U9") (pin "8") (pinfunction "OUT_8") (pintype "output"))
    )
    (net (code "14") (name "/PILOT_REF") (class "Default")
      (node (ref "C38") (pin "2") (pinfunction "2_2") (pintype "passive"))
      (node (ref "R45") (pin "2") (pinfunction "2_2") (pintype "passive"))
      (node (ref "R46") (pin "1") (pinfunction "1_1") (pintype "passive"))
      (node (ref "U5") (pin "18") (pinfunction "PILOT_18") (pintype "bidirectional"))
    )
    (net (code "15") (name "/RDS") (class "Default")
      (node (ref "R56") (pin "1") (pinfunction "1_1") (pintype "passive"))
      (node (ref "R59-RDS") (pin "1") (pinfunction "1_1") (pintype "passive"))
      (node (ref "U9") (pin "14") (pinfunction "OUT_14") (pintype "output"))
    )
    (net (code "16") (name "/RDS_DAC") (class "Default")
      (node (ref "C39") (pin "2") (pinfunction "2_2") (pintype "passive"))
      (node (ref "C42") (pin "1") (pinfunction "1_1") (pintype "passive"))
      (node (ref "C43") (pin "1") (pinfunction "1_1") (pintype "passive"))
      (node (ref "C58") (pin "2") (pinfunction "2_2") (pintype "passive"))
      (node (ref "R52") (pin "1") (pinfunction "1_1") (pintype "passive"))
    )
    (net (code "17") (name "/R_IN") (class "Default")
      (node (ref "C60") (pin "1") (pinfunction "1_1") (pintype "passive"))
      (node (ref "L11") (pin "2") (pinfunction "2_2") (pintype "passive"))
      (node (ref "R6") (pin "3") (pinfunction "CW_3") (pintype "passive"))
    )
    (net (code "18") (name "/R_SENSE") (class "Default")
      (node (ref "C47") (pin "1") (pinfunction "1_1") (pintype "passive"))
      (node (ref "R11") (pin "1") (pinfunction "1_1") (pintype "passive"))
      (node (ref "R13") (pin "2") (pinfunction "2_2") (pintype "passive"))
      (node (ref "U6") (pin "8") (pinfunction "OUT_8") (pintype "output"))
    )
    (net (code "19") (name "/SGND") (class "Default")
      (node (ref "JP3") (pin "3") (pinfunction "3_3") (pintype "passive"))
      (node (ref "L7") (pin "2") (pinfunction "2_2") (pintype "passive"))
    )
    (net (code "20") (name "/SRXD") (class "Default")
      (node (ref "JP3") (pin "1") (pinfunction "1_1") (pintype "passive"))
      (node (ref "R21") (pin "1") (pinfunction "1_1") (pintype "passive"))
    )
    (net (code "21") (name "/STXD") (class "Default")
      (node (ref "JP3") (pin "2") (pinfunction "2_2") (pintype "passive"))
      (node (ref "R14") (pin "2") (pinfunction "2_2") (pintype "passive"))
    )
    (net (code "22") (name "/VGND") (class "Default")
      (node (ref "JP6") (pin "2") (pinfunction "2_2") (pintype "passive"))
      (node (ref "L6") (pin "2") (pinfunction "2_2") (pintype "passive"))
    )
    (net (code "23") (name "/VREF") (class "Default")
      (node (ref "C12") (pin "2") (pinfunction "2_2") (pintype "passive"))
      (node (ref "C15") (pin "2") (pinfunction "2_2") (pintype "passive"))
      (node (ref "R1") (pin "2") (pinfunction "2_2") (pintype "passive"))
      (node (ref "U6") (pin "10") (pinfunction "+IN_10") (pintype "input"))
      (node (ref "U6") (pin "5") (pinfunction "+IN_5") (pintype "input"))
      (node (ref "U9") (pin "10") (pinfunction "+IN_10") (pintype "input"))
      (node (ref "U9") (pin "12") (pinfunction "+IN_12") (pintype "input"))
      (node (ref "U9") (pin "3") (pinfunction "+IN_3") (pintype "input"))
      (node (ref "U9") (pin "5") (pinfunction "+IN_5") (pintype "input"))
    )
    (net (code "24") (name "GND") (class "Default")
      (node (ref "C1") (pin "2") (pinfunction "2_2") (pintype "passive"))
      (node (ref "C10") (pin "2") (pinfunction "2_2") (pintype "passive"))
      (node (ref "C11") (pin "2") (pinfunction "2_2") (pintype "passive"))
      (node (ref "C12") (pin "1") (pinfunction "1_1") (pintype "passive"))
      (node (ref "C13") (pin "2") (pinfunction "2_2") (pintype "passive"))
      (node (ref "C14") (pin "2") (pinfunction "2_2") (pintype "passive"))
      (node (ref "C15") (pin "1") (pinfunction "1_1") (pintype "passive"))
      (node (ref "C16") (pin "2") (pinfunction "2_2") (pintype "passive"))
      (node (ref "C19") (pin "2") (pinfunction "2_2") (pintype "passive"))
      (node (ref "C2") (pin "2") (pinfunction "2_2") (pintype "passive"))
      (node (ref "C20") (pin "2") (pinfunction "2_2") (pintype "passive"))
      (node (ref "C23") (pin "1") (pinfunction "1_1") (pintype "passive"))
      (node (ref "C24") (pin "1") (pinfunction "1_1") (pintype "passive"))
      (node (ref "C27") (pin "2") (pinfunction "2_2") (pintype "passive"))
      (node (ref "C3") (pin "2") (pinfunction "2_2") (pintype "passive"))
      (node (ref "C30") (pin "1") (pinfunction "1_1") (pintype "passive"))
      (node (ref "C31") (pin "1") (pinfunction "1_1") (pintype "passive"))
      (node (ref "C4") (pin "2") (pinfunction "2_2") (pintype "passive"))
      (node (ref "C41") (pin "1") (pinfunction "1_1") (pintype "passive"))
      (node (ref "C42") (pin "2") (pinfunction "2_2") (pintype "passive"))
      (node (ref "C43") (pin "2") (pinfunction "2_2") (pintype "passive"))
      (node (ref "C46") (pin "1") (pinfunction "1_1") (pintype "passive"))
      (node (ref "C5") (pin "1") (pinfunction "1_1") (pintype "passive"))
      (node (ref "C52") (pin "2") (pinfunction "2_2") (pintype "passive"))
      (node (ref "C53") (pin "2") (pinfunction "2_2") (pintype "passive"))
      (node (ref "C55") (pin "1") (pinfunction "1_1") (pintype "passive"))
      (node (ref "C56") (pin "1") (pinfunction "1_1") (pintype "passive"))
      (node (ref "C57") (pin "1") (pinfunction "1_1") (pintype "passive"))
      (node (ref "C59") (pin "1") (pinfunction "1_1") (pintype "passive"))
      (node (ref "C6") (pin "1") (pinfunction "1_1") (pintype "passive"))
      (node (ref "C60") (pin "2") (pinfunction "2_2") (pintype "passive"))
      (node (ref "C61") (pin "2") (pinfunction "2_2") (pintype "passive"))
      (node (ref "C62") (pin "2") (pinfunction "2_2") (pintype "passive"))
      (node (ref "C7") (pin "1") (pinfunction "1_1") (pintype "passive"))
      (node (ref "C8") (pin "1") (pinfunction "1_1") (pintype "passive"))
      (node (ref "C9") (pin "2") (pinfunction "2_2") (pintype "passive"))
      (node (ref "JP1") (pin "1") (pinfunction "1_1") (pintype "passive"))
      (node (ref "JP4") (pin "2") (pinfunction "2_2") (pintype "passive"))
      (node (ref "JP7") (pin "2") (pinfunction "2_2") (pintype "passive"))
      (node (ref "L4") (pin "1") (pinfunction "L1_1") (pintype "passive"))
      (node (ref "L5") (pin "1") (pinfunction "1_1") (pintype "passive"))
      (node (ref "L6") (pin "1") (pinfunction "1_1") (pintype "passive"))
      (node (ref "L7") (pin "1") (pinfunction "1_1") (pintype "passive"))
      (node (ref "LED1") (pin "C") (pinfunction "C_C") (pintype "passive"))
      (node (ref "R34") (pin "2") (pinfunction "2_2") (pintype "passive"))
      (node (ref "R35") (pin "1") (pinfunction "1_1") (pintype "passive"))
      (node (ref "R4") (pin "2") (pinfunction "2_2") (pintype "passive"))
      (node (ref "R46") (pin "2") (pinfunction "2_2") (pintype "passive"))
      (node (ref "R48") (pin "2") (pinfunction "2_2") (pintype "passive"))
      (node (ref "R5") (pin "1") (pinfunction "CCW_1") (pintype "passive"))
      (node (ref "R57-MPX") (pin "3") (pinfunction "3_3") (pintype "passive"))
      (node (ref "R58-PILOT") (pin "3") (pinfunction "3_3") (pintype "passive"))
      (node (ref "R59-RDS") (pin "3") (pinfunction "3_3") (pintype "passive"))
      (node (ref "R6") (pin "1") (pinfunction "CCW_1") (pintype "passive"))
      (node (ref "R60") (pin "1") (pinfunction "1_1") (pintype "passive"))
      (node (ref "R61") (pin "1") (pinfunction "1_1") (pintype "passive"))
      (node (ref "R62") (pin "1") (pinfunction "1_1") (pintype "passive"))
      (node (ref "R63") (pin "1") (pinfunction "1_1") (pintype "passive"))
      (node (ref "R72-VUR") (pin "3") (pinfunction "3_3") (pintype "passive"))
      (node (ref "R73-VUL") (pin "3") (pinfunction "3_3") (pintype "passive"))
      (node (ref "R74") (pin "2") (pinfunction "2_2") (pintype "passive"))
      (node (ref "SW1") (pin "P$2") (pinfunction "P$2_P$2") (pintype "passive"))
      (node (ref "U1") (pin "2") (pinfunction "COMMON_2") (pintype "passive"))
      (node (ref "U2") (pin "2") (pinfunction "GND_2") (pintype "power_in"))
      (node (ref "U3") (pin "2") (pinfunction "GND_2") (pintype "power_in"))
      (node (ref "U4") (pin "2") (pinfunction "GND_2") (pintype "power_in"))
      (node (ref "U5") (pin "19") (pinfunction "_SYNC_19") (pintype "bidirectional"))
      (node (ref "U5") (pin "20") (pinfunction "VSS_20") (pintype "power_in"))
      (node (ref "U6") (pin "11") (pinfunction "VSS_11") (pintype "power_in"))
      (node (ref "U7") (pin "4") (pinfunction "GND_4") (pintype "passive"))
      (node (ref "U8") (pin "4") (pinfunction "VCC-_4") (pintype "power_in"))
      (node (ref "U9") (pin "11") (pinfunction "VSS_11") (pintype "power_in"))
    )
    (net (code "25") (name "Net-(C7-Pad2)") (class "Default")
      (node (ref "C7") (pin "2") (pinfunction "2_2") (pintype "passive"))
      (node (ref "L9") (pin "2") (pinfunction "2_2") (pintype "passive"))
      (node (ref "R75") (pin "2") (pinfunction "2_2") (pintype "passive"))
    )
    (net (code "26") (name "Net-(C17-Pad2)") (class "Default")
      (node (ref "C17") (pin "2") (pinfunction "2_2") (pintype "passive"))
      (node (ref "R7") (pin "2") (pinfunction "2_2") (pintype "passive"))
    )
    (net (code "27") (name "Net-(C18-Pad2)") (class "Default")
      (node (ref "C18") (pin "2") (pinfunction "2_2") (pintype "passive"))
      (node (ref "R8") (pin "2") (pinfunction "2_2") (pintype "passive"))
    )
    (net (code "28") (name "Net-(C21-Pad1)") (class "Default")
      (node (ref "C21") (pin "1") (pinfunction "1_1") (pintype "passive"))
      (node (ref "R12") (pin "1") (pinfunction "1_1") (pintype "passive"))
      (node (ref "R15") (pin "2") (pinfunction "2_2") (pintype "passive"))
    )
    (net (code "29") (name "Net-(C22-Pad1)") (class "Default")
      (node (ref "C22") (pin "1") (pinfunction "1_1") (pintype "passive"))
      (node (ref "R13") (pin "1") (pinfunction "1_1") (pintype "passive"))
      (node (ref "R16") (pin "2") (pinfunction "2_2") (pintype "passive"))
    )
    (net (code "30") (name "Net-(C25-Pad1)") (class "Default")
      (node (ref "C25") (pin "1") (pinfunction "1_1") (pintype "passive"))
      (node (ref "C28") (pin "1") (pinfunction "1_1") (pintype "passive"))
      (node (ref "R19") (pin "1") (pinfunction "1_1") (pintype "passive"))
    )
    (net (code "31") (name "Net-(C25-Pad2)") (class "Default")
      (node (ref "C25") (pin "2") (pinfunction "2_2") (pintype "passive"))
      (node (ref "R17") (pin "1") (pinfunction "1_1") (pintype "passive"))
      (node (ref "R19") (pin "2") (pinfunction "2_2") (pintype "passive"))
    )
    (net (code "32") (name "Net-(C26-Pad1)") (class "Default")
      (node (ref "C26") (pin "1") (pinfunction "1_1") (pintype "passive"))
      (node (ref "C29") (pin "1") (pinfunction "1_1") (pintype "passive"))
      (node (ref "R20") (pin "1") (pinfunction "1_1") (pintype "passive"))
    )
    (net (code "33") (name "Net-(C26-Pad2)") (class "Default")
      (node (ref "C26") (pin "2") (pinfunction "2_2") (pintype "passive"))
      (node (ref "R18") (pin "1") (pinfunction "1_1") (pintype "passive"))
      (node (ref "R20") (pin "2") (pinfunction "2_2") (pintype "passive"))
    )
    (net (code "34") (name "Net-(C32-Pad1)") (class "Default")
      (node (ref "C32") (pin "1") (pinfunction "1_1") (pintype "passive"))
      (node (ref "R24") (pin "2") (pinfunction "2_2") (pintype "passive"))
    )
    (net (code "35") (name "Net-(C34-Pad2)") (class "Default")
      (node (ref "C34") (pin "2") (pinfunction "2_2") (pintype "passive"))
      (node (ref "R33") (pin "1") (pinfunction "1_1") (pintype "passive"))
    )
    (net (code "36") (name "Net-(C35-Pad1)") (class "Default")
      (node (ref "C35") (pin "1") (pinfunction "1_1") (pintype "passive"))
      (node (ref "XTAL1") (pin "2") (pinfunction "2_2") (pintype "passive"))
    )
    (net (code "37") (name "Net-(C37-Pad1)") (class "Default")
      (node (ref "C37") (pin "1") (pinfunction "1_1") (pintype "passive"))
      (node (ref "R44") (pin "2") (pinfunction "2_2") (pintype "passive"))
    )
    (net (code "38") (name "Net-(C39-Pad1)") (class "Default")
      (node (ref "C39") (pin "1") (pinfunction "1_1") (pintype "passive"))
      (node (ref "R43") (pin "2") (pinfunction "2_2") (pintype "passive"))
    )
    (net (code "39") (name "Net-(C44-Pad2)") (class "Default")
      (node (ref "C44") (pin "2") (pinfunction "2_2") (pintype "passive"))
      (node (ref "R50") (pin "2") (pinfunction "2_2") (pintype "passive"))
    )
    (net (code "40") (name "Net-(C45-Pad2)") (class "Default")
      (node (ref "C45") (pin "2") (pinfunction "2_2") (pintype "passive"))
      (node (ref "R51") (pin "2") (pinfunction "2_2") (pintype "passive"))
    )
    (net (code "41") (name "Net-(C46-Pad2)") (class "Default")
      (node (ref "C46") (pin "2") (pinfunction "2_2") (pintype "passive"))
      (node (ref "R47") (pin "2") (pinfunction "2_2") (pintype "passive"))
      (node (ref "R48") (pin "1") (pinfunction "1_1") (pintype "passive"))
      (node (ref "R49") (pin "2") (pinfunction "2_2") (pintype "passive"))
    )
    (net (code "42") (name "Net-(C49-Pad1)") (class "Default")
      (node (ref "C49") (pin "1") (pinfunction "1_1") (pintype "passive"))
      (node (ref "R57-MPX") (pin "2") (pinfunction "2_2") (pintype "passive"))
    )
    (net (code "43") (name "Net-(C49-Pad2)") (class "Default")
      (node (ref "C49") (pin "2") (pinfunction "2_2") (pintype "passive"))
      (node (ref "R64") (pin "2") (pinfunction "2_2") (pintype "passive"))
    )
    (net (code "44") (name "Net-(C50-Pad1)") (class "Default")
      (node (ref "C50") (pin "1") (pinfunction "1_1") (pintype "passive"))
      (node (ref "R58-PILOT") (pin "2") (pinfunction "2_2") (pintype "passive"))
    )
    (net (code "45") (name "Net-(C50-Pad2)") (class "Default")
      (node (ref "C50") (pin "2") (pinfunction "2_2") (pintype "passive"))
      (node (ref "R65") (pin "2") (pinfunction "2_2") (pintype "passive"))
    )
    (net (code "46") (name "Net-(C51-Pad1)") (class "Default")
      (node (ref "C51") (pin "1") (pinfunction "1_1") (pintype "passive"))
      (node (ref "R59-RDS") (pin "2") (pinfunction "2_2") (pintype "passive"))
    )
    (net (code "47") (name "Net-(C51-Pad2)") (class "Default")
      (node (ref "C51") (pin "2") (pinfunction "2_2") (pintype "passive"))
      (node (ref "R66") (pin "2") (pinfunction "2_2") (pintype "passive"))
    )
    (net (code "48") (name "Net-(C52-Pad1)") (class "Default")
      (node (ref "C52") (pin "1") (pinfunction "1_1") (pintype "passive"))
      (node (ref "R69") (pin "2") (pinfunction "2_2") (pintype "passive"))
      (node (ref "R72-VUR") (pin "1") (pinfunction "1_1") (pintype "passive"))
    )
    (net (code "49") (name "Net-(C53-Pad1)") (class "Default")
      (node (ref "C53") (pin "1") (pinfunction "1_1") (pintype "passive"))
      (node (ref "R70") (pin "2") (pinfunction "2_2") (pintype "passive"))
      (node (ref "R73-VUL") (pin "1") (pinfunction "1_1") (pintype "passive"))
    )
    (net (code "50") (name "Net-(C54-Pad2)") (class "Default")
      (node (ref "C54") (pin "2") (pinfunction "2_2") (pintype "passive"))
      (node (ref "R74") (pin "1") (pinfunction "1_1") (pintype "passive"))
      (node (ref "R75") (pin "1") (pinfunction "1_1") (pintype "passive"))
    )
    (net (code "51") (name "Net-(C58-Pad1)") (class "Default")
      (node (ref "C58") (pin "1") (pinfunction "1_1") (pintype "passive"))
      (node (ref "R53") (pin "2") (pinfunction "2_2") (pintype "passive"))
    )
    (net (code "52") (name "Net-(D2-PadC)") (class "Default")
      (node (ref "D2") (pin "C") (pinfunction "C_C") (pintype "passive"))
      (node (ref "R67") (pin "2") (pinfunction "2_2") (pintype "passive"))
      (node (ref "R69") (pin "1") (pinfunction "1_1") (pintype "passive"))
    )
    (net (code "53") (name "Net-(D3-PadC)") (class "Default")
      (node (ref "D3") (pin "C") (pinfunction "C_C") (pintype "passive"))
      (node (ref "R68") (pin "2") (pinfunction "2_2") (pintype "passive"))
      (node (ref "R70") (pin "1") (pinfunction "1_1") (pintype "passive"))
    )
    (net (code "54") (name "Net-(JP4-Pad1)") (class "Default")
      (node (ref "JP4") (pin "1") (pinfunction "1_1") (pintype "passive"))
      (node (ref "L9") (pin "1") (pinfunction "1_1") (pintype "passive"))
    )
    (net (code "55") (name "Net-(JP6-Pad1)") (class "Default")
      (node (ref "JP6") (pin "1") (pinfunction "1_1") (pintype "passive"))
      (node (ref "R58") (pin "1") (pinfunction "1_1") (pintype "passive"))
    )
    (net (code "56") (name "Net-(JP6-Pad3)") (class "Default")
      (node (ref "JP6") (pin "3") (pinfunction "3_3") (pintype "passive"))
      (node (ref "R57") (pin "2") (pinfunction "2_2") (pintype "passive"))
    )
    (net (code "57") (name "Net-(JP7-Pad1)") (class "Default")
      (node (ref "JP7") (pin "1") (pinfunction "1_1") (pintype "passive"))
      (node (ref "L11") (pin "1") (pinfunction "1_1") (pintype "passive"))
    )
    (net (code "58") (name "Net-(JP7-Pad3)") (class "Default")
      (node (ref "JP7") (pin "3") (pinfunction "3_3") (pintype "passive"))
      (node (ref "L10") (pin "2") (pinfunction "2_2") (pintype "passive"))
    )
    (net (code "59") (name "Net-(L3A-L1)") (class "Default")
      (node (ref "C33") (pin "2") (pinfunction "2_2") (pintype "passive"))
      (node (ref "C36") (pin "1") (pinfunction "1_1") (pintype "passive"))
      (node (ref "L3") (pin "1") (pinfunction "L1_1") (pintype "passive"))
      (node (ref "R24") (pin "1") (pinfunction "1_1") (pintype "passive"))
    )
    (net (code "60") (name "Net-(L3A-L2)") (class "Default")
      (node (ref "C36") (pin "2") (pinfunction "2_2") (pintype "passive"))
      (node (ref "C40") (pin "2") (pinfunction "2_2") (pintype "passive"))
      (node (ref "C44") (pin "1") (pinfunction "1_1") (pintype "passive"))
      (node (ref "L3") (pin "3") (pinfunction "L2_3") (pintype "passive"))
    )
    (net (code "61") (name "Net-(L4A-L2)") (class "Default")
      (node (ref "C41") (pin "2") (pinfunction "2_2") (pintype "passive"))
      (node (ref "C45") (pin "1") (pinfunction "1_1") (pintype "passive"))
      (node (ref "L4") (pin "3") (pinfunction "L2_3") (pintype "passive"))
      (node (ref "R44") (pin "1") (pinfunction "1_1") (pintype "passive"))
    )
    (net (code "62") (name "Net-(L5-Pad2)") (class "Default")
      (node (ref "L5") (pin "2") (pinfunction "2_2") (pintype "passive"))
      (node (ref "R52") (pin "2") (pinfunction "2_2") (pintype "passive"))
    )
    (net (code "63") (name "Net-(LED1-PadA)") (class "Default")
      (node (ref "LED1") (pin "A") (pinfunction "A_A") (pintype "passive"))
      (node (ref "R23") (pin "2") (pinfunction "2_2") (pintype "passive"))
    )
    (net (code "64") (name "Net-(R5-W)") (class "Default")
      (node (ref "C17") (pin "1") (pinfunction "1_1") (pintype "passive"))
      (node (ref "R5") (pin "2") (pinfunction "W_2") (pintype "passive"))
    )
    (net (code "65") (name "Net-(R6-W)") (class "Default")
      (node (ref "C18") (pin "1") (pinfunction "1_1") (pintype "passive"))
      (node (ref "R6") (pin "2") (pinfunction "W_2") (pintype "passive"))
    )
    (net (code "66") (name "Net-(R25-Pad1)") (class "Default")
      (node (ref "R25") (pin "1") (pinfunction "1_1") (pintype "passive"))
      (node (ref "R35") (pin "2") (pinfunction "2_2") (pintype "passive"))
      (node (ref "R36") (pin "1") (pinfunction "1_1") (pintype "passive"))
    )
    (net (code "67") (name "Net-(R26-Pad1)") (class "Default")
      (node (ref "R26") (pin "1") (pinfunction "1_1") (pintype "passive"))
      (node (ref "R36") (pin "2") (pinfunction "2_2") (pintype "passive"))
      (node (ref "R37") (pin "1") (pinfunction "1_1") (pintype "passive"))
    )
    (net (code "68") (name "Net-(R27-Pad1)") (class "Default")
      (node (ref "R27") (pin "1") (pinfunction "1_1") (pintype "passive"))
      (node (ref "R37") (pin "2") (pinfunction "2_2") (pintype "passive"))
      (node (ref "R38") (pin "1") (pinfunction "1_1") (pintype "passive"))
    )
    (net (code "69") (name "Net-(R28-Pad1)") (class "Default")
      (node (ref "R28") (pin "1") (pinfunction "1_1") (pintype "passive"))
      (node (ref "R38") (pin "2") (pinfunction "2_2") (pintype "passive"))
      (node (ref "R39") (pin "1") (pinfunction "1_1") (pintype "passive"))
    )
    (net (code "70") (name "Net-(R29-Pad1)") (class "Default")
      (node (ref "R29") (pin "1") (pinfunction "1_1") (pintype "passive"))
      (node (ref "R39") (pin "2") (pinfunction "2_2") (pintype "passive"))
      (node (ref "R40") (pin "1") (pinfunction "1_1") (pintype "passive"))
    )
    (net (code "71") (name "Net-(R30-Pad1)") (class "Default")
      (node (ref "R30") (pin "1") (pinfunction "1_1") (pintype "passive"))
      (node (ref "R40") (pin "2") (pinfunction "2_2") (pintype "passive"))
      (node (ref "R41") (pin "1") (pinfunction "1_1") (pintype "passive"))
    )
    (net (code "72") (name "Net-(R31-Pad1)") (class "Default")
      (node (ref "R31") (pin "1") (pinfunction "1_1") (pintype "passive"))
      (node (ref "R41") (pin "2") (pinfunction "2_2") (pintype "passive"))
      (node (ref "R42") (pin "1") (pinfunction "1_1") (pintype "passive"))
    )
    (net (code "73") (name "Net-(R32-Pad1)") (class "Default")
      (node (ref "R32") (pin "1") (pinfunction "1_1") (pintype "passive"))
      (node (ref "R42") (pin "2") (pinfunction "2_2") (pintype "passive"))
      (node (ref "R43") (pin "1") (pinfunction "1_1") (pintype "passive"))
    )
    (net (code "74") (name "Net-(T1-D)") (class "Default")
      (node (ref "C9") (pin "1") (pinfunction "1_1") (pintype "passive"))
      (node (ref "T1") (pin "1") (pinfunction "D_1") (pintype "passive"))
      (node (ref "U2") (pin "5") (pinfunction "OUT_5") (pintype "output"))
    )
    (net (code "75") (name "Net-(T1-G)") (class "Default")
      (node (ref "R4") (pin "1") (pinfunction "1_1") (pintype "passive"))
      (node (ref "T1") (pin "3") (pinfunction "G_3") (pintype "passive"))
    )
    (net (code "76") (name "Net-(T2-B)") (class "Default")
      (node (ref "R33") (pin "2") (pinfunction "2_2") (pintype "passive"))
      (node (ref "R49") (pin "1") (pinfunction "1_1") (pintype "passive"))
      (node (ref "T2") (pin "1") (pinfunction "B_1") (pintype "passive"))
    )
    (net (code "77") (name "Net-(T2-E)") (class "Default")
      (node (ref "C38") (pin "1") (pinfunction "1_1") (pintype "passive"))
      (node (ref "R34") (pin "1") (pinfunction "1_1") (pintype "passive"))
      (node (ref "T2") (pin "2") (pinfunction "E_2") (pintype "passive"))
    )
    (net (code "78") (name "Net-(U1-OUT)") (class "Default")
      (node (ref "C8") (pin "2") (pinfunction "2_2") (pintype "passive"))
      (node (ref "R1") (pin "1") (pinfunction "1_1") (pintype "passive"))
      (node (ref "U1") (pin "3") (pinfunction "OUT_3") (pintype "output"))
    )
    (net (code "79") (name "Net-(U3-OUT)") (class "Default")
      (node (ref "C10") (pin "1") (pinfunction "1_1") (pintype "passive"))
      (node (ref "R2") (pin "1") (pinfunction "1_1") (pintype "passive"))
      (node (ref "U3") (pin "5") (pinfunction "OUT_5") (pintype "output"))
    )
    (net (code "80") (name "Net-(U4-OUT)") (class "Default")
      (node (ref "C11") (pin "1") (pinfunction "1_1") (pintype "passive"))
      (node (ref "R3") (pin "1") (pinfunction "1_1") (pintype "passive"))
      (node (ref "U4") (pin "5") (pinfunction "OUT_5") (pintype "output"))
    )
    (net (code "81") (name "Net-(U5-DA0)") (class "Default")
      (node (ref "R25") (pin "2") (pinfunction "2_2") (pintype "passive"))
      (node (ref "U5") (pin "14") (pinfunction "DA0_14") (pintype "bidirectional"))
    )
    (net (code "82") (name "Net-(U5-DA1)") (class "Default")
      (node (ref "R26") (pin "2") (pinfunction "2_2") (pintype "passive"))
      (node (ref "U5") (pin "15") (pinfunction "DA1_15") (pintype "bidirectional"))
    )
    (net (code "83") (name "Net-(U5-DA2)") (class "Default")
      (node (ref "R27") (pin "2") (pinfunction "2_2") (pintype "passive"))
      (node (ref "U5") (pin "16") (pinfunction "DA2_16") (pintype "bidirectional"))
    )
    (net (code "84") (name "Net-(U5-DA3)") (class "Default")
      (node (ref "R28") (pin "2") (pinfunction "2_2") (pintype "passive"))
      (node (ref "U5") (pin "9") (pinfunction "DA3_9") (pintype "bidirectional"))
    )
    (net (code "85") (name "Net-(U5-DA4)") (class "Default")
      (node (ref "R29") (pin "2") (pinfunction "2_2") (pintype "passive"))
      (node (ref "U5") (pin "8") (pinfunction "DA4_8") (pintype "bidirectional"))
    )
    (net (code "86") (name "Net-(U5-DA5)") (class "Default")
      (node (ref "R30") (pin "2") (pinfunction "2_2") (pintype "passive"))
      (node (ref "U5") (pin "7") (pinfunction "DA5_7") (pintype "bidirectional"))
    )
    (net (code "87") (name "Net-(U5-DA6)") (class "Default")
      (node (ref "R31") (pin "2") (pinfunction "2_2") (pintype "passive"))
      (node (ref "U5") (pin "6") (pinfunction "DA6_6") (pintype "bidirectional"))
    )
    (net (code "88") (name "Net-(U5-DA7)") (class "Default")
      (node (ref "R32") (pin "2") (pinfunction "2_2") (pintype "passive"))
      (node (ref "U5") (pin "5") (pinfunction "DA7_5") (pintype "bidirectional"))
    )
    (net (code "89") (name "Net-(U5-LED{slash}SCL)") (class "Default")
      (node (ref "R23") (pin "1") (pinfunction "1_1") (pintype "passive"))
      (node (ref "U5") (pin "11") (pinfunction "LED/SCL_11") (pintype "bidirectional"))
    )
    (net (code "90") (name "Net-(U5-MODE)") (class "Default")
      (node (ref "C5") (pin "2") (pinfunction "2_2") (pintype "passive"))
      (node (ref "C6") (pin "2") (pinfunction "2_2") (pintype "passive"))
      (node (ref "L8") (pin "2") (pinfunction "2_2") (pintype "passive"))
      (node (ref "R9") (pin "1") (pinfunction "1_1") (pintype "passive"))
      (node (ref "U5") (pin "1") (pinfunction "VDD_1") (pintype "power_in"))
      (node (ref "U5") (pin "17") (pinfunction "MODE_17") (pintype "bidirectional"))
    )
    (net (code "91") (name "Net-(U5-OSC_IN)") (class "Default")
      (node (ref "C19") (pin "1") (pinfunction "1_1") (pintype "passive"))
      (node (ref "U5") (pin "2") (pinfunction "OSC_IN_2") (pintype "bidirectional"))
      (node (ref "X1") (pin "1") (pinfunction "1_1") (pintype "passive"))
    )
    (net (code "92") (name "Net-(U5-OSC_OUT)") (class "Default")
      (node (ref "C16") (pin "1") (pinfunction "1_1") (pintype "passive"))
      (node (ref "U5") (pin "3") (pinfunction "OSC_OUT_3") (pintype "bidirectional"))
      (node (ref "X1") (pin "2") (pinfunction "2_2") (pintype "passive"))
    )
    (net (code "93") (name "Net-(U5-RXD{slash}TA)") (class "Default")
      (node (ref "R21") (pin "2") (pinfunction "2_2") (pintype "passive"))
      (node (ref "U5") (pin "12") (pinfunction "RXD/TA_12") (pintype "bidirectional"))
    )
    (net (code "94") (name "Net-(U5-TXD{slash}LED)") (class "Default")
      (node (ref "R14") (pin "1") (pinfunction "1_1") (pintype "passive"))
      (node (ref "U5") (pin "10") (pinfunction "TXD/LED_10") (pintype "bidirectional"))
    )
    (net (code "95") (name "Net-(U5-_RESET)") (class "Default")
      (node (ref "C20") (pin "1") (pinfunction "1_1") (pintype "passive"))
      (node (ref "R9") (pin "2") (pinfunction "2_2") (pintype "passive"))
      (node (ref "SW1") (pin "P$1") (pinfunction "P$1_P$1") (pintype "passive"))
      (node (ref "U5") (pin "4") (pinfunction "_RESET_4") (pintype "bidirectional"))
    )
    (net (code "96") (name "Net-(U6A-+IN)") (class "Default")
      (node (ref "C23") (pin "2") (pinfunction "2_2") (pintype "passive"))
      (node (ref "R15") (pin "1") (pinfunction "1_1") (pintype "passive"))
      (node (ref "U6") (pin "3") (pinfunction "+IN_3") (pintype "input"))
    )
    (net (code "97") (name "Net-(U6A--IN)") (class "Default")
      (node (ref "C21") (pin "2") (pinfunction "2_2") (pintype "passive"))
      (node (ref "R17") (pin "2") (pinfunction "2_2") (pintype "passive"))
      (node (ref "U6") (pin "1") (pinfunction "OUT_1") (pintype "output"))
      (node (ref "U6") (pin "2") (pinfunction "-IN_2") (pintype "input"))
    )
    (net (code "98") (name "Net-(U6B--IN)") (class "Default")
      (node (ref "R10") (pin "2") (pinfunction "2_2") (pintype "passive"))
      (node (ref "R7") (pin "1") (pinfunction "1_1") (pintype "passive"))
      (node (ref "U6") (pin "6") (pinfunction "-IN_6") (pintype "input"))
    )
    (net (code "99") (name "Net-(U6C--IN)") (class "Default")
      (node (ref "R11") (pin "2") (pinfunction "2_2") (pintype "passive"))
      (node (ref "R8") (pin "1") (pinfunction "1_1") (pintype "passive"))
      (node (ref "U6") (pin "9") (pinfunction "-IN_9") (pintype "input"))
    )
    (net (code "100") (name "Net-(U6D-+IN)") (class "Default")
      (node (ref "C24") (pin "2") (pinfunction "2_2") (pintype "passive"))
      (node (ref "R16") (pin "1") (pinfunction "1_1") (pintype "passive"))
      (node (ref "U6") (pin "12") (pinfunction "+IN_12") (pintype "input"))
    )
    (net (code "101") (name "Net-(U6D--IN)") (class "Default")
      (node (ref "C22") (pin "2") (pinfunction "2_2") (pintype "passive"))
      (node (ref "R18") (pin "2") (pinfunction "2_2") (pintype "passive"))
      (node (ref "U6") (pin "13") (pinfunction "-IN_13") (pintype "input"))
      (node (ref "U6") (pin "14") (pinfunction "OUT_14") (pintype "output"))
    )
    (net (code "102") (name "Net-(U7-1-CH_INPUT)") (class "Default")
      (node (ref "C29") (pin "2") (pinfunction "2_2") (pintype "passive"))
      (node (ref "U7") (pin "1") (pinfunction "1-CH_INPUT_1") (pintype "input"))
    )
    (net (code "103") (name "Net-(U7-2-CH_INPUT)") (class "Default")
      (node (ref "C28") (pin "2") (pinfunction "2_2") (pintype "passive"))
      (node (ref "U7") (pin "14") (pinfunction "2-CH_INPUT_14") (pintype "input"))
    )
    (net (code "104") (name "Net-(U7-AC_BYPASS)") (class "Default")
      (node (ref "C31") (pin "2") (pinfunction "2_2") (pintype "passive"))
      (node (ref "U7") (pin "5") (pinfunction "AC_BYPASS_5") (pintype "passive"))
    )
    (net (code "105") (name "Net-(U7-AC_BYPASS_2)") (class "Default")
      (node (ref "C30") (pin "2") (pinfunction "2_2") (pintype "passive"))
      (node (ref "U7") (pin "3") (pinfunction "AC_BYPASS_2_3") (pintype "passive"))
    )
    (net (code "106") (name "Net-(U7-MPX_OUTPUT)") (class "Default")
      (node (ref "C32") (pin "2") (pinfunction "2_2") (pintype "passive"))
      (node (ref "U7") (pin "9") (pinfunction "MPX_OUTPUT_9") (pintype "output"))
    )
    (net (code "107") (name "Net-(U7-PILOUT_OUTPUT)") (class "Default")
      (node (ref "C34") (pin "1") (pinfunction "1_1") (pintype "passive"))
      (node (ref "C37") (pin "2") (pinfunction "2_2") (pintype "passive"))
      (node (ref "U7") (pin "8") (pinfunction "PILOUT_OUTPUT_8") (pintype "output"))
    )
    (net (code "108") (name "Net-(U7-TO_CAPACITOR)") (class "Default")
      (node (ref "C35") (pin "2") (pinfunction "2_2") (pintype "passive"))
      (node (ref "U7") (pin "7") (pinfunction "TO_CAPACITOR_7") (pintype "passive"))
    )
    (net (code "109") (name "Net-(U7-TO_CRYSTAL)") (class "Default")
      (node (ref "U7") (pin "6") (pinfunction "TO_CRYSTAL_6") (pintype "passive"))
      (node (ref "XTAL1") (pin "1") (pinfunction "1_1") (pintype "passive"))
    )
    (net (code "110") (name "Net-(U7-TRIMMING)") (class "Default")
      (node (ref "R22") (pin "1") (pinfunction "1_1") (pintype "passive"))
      (node (ref "U7") (pin "12") (pinfunction "TRIMMING_12") (pintype "passive"))
    )
    (net (code "111") (name "Net-(U7-TRIMMING_2)") (class "Default")
      (node (ref "R22") (pin "3") (pinfunction "3_3") (pintype "passive"))
      (node (ref "U7") (pin "11") (pinfunction "TRIMMING_2_11") (pintype "passive"))
    )
    (net (code "112") (name "Net-(U8A-+IN)") (class "Default")
      (node (ref "C47") (pin "2") (pinfunction "2_2") (pintype "passive"))
      (node (ref "R62") (pin "2") (pinfunction "2_2") (pintype "passive"))
      (node (ref "U8") (pin "3") (pinfunction "+IN_3") (pintype "input"))
    )
    (net (code "113") (name "Net-(U8A--IN)") (class "Default")
      (node (ref "R60") (pin "2") (pinfunction "2_2") (pintype "passive"))
      (node (ref "R67") (pin "1") (pinfunction "1_1") (pintype "passive"))
      (node (ref "U8") (pin "2") (pinfunction "-IN_2") (pintype "input"))
    )
    (net (code "114") (name "Net-(U8A-OUT)") (class "Default")
      (node (ref "D2") (pin "A") (pinfunction "A_A") (pintype "passive"))
      (node (ref "U8") (pin "1") (pinfunction "OUT_1") (pintype "output"))
    )
    (net (code "115") (name "Net-(U8B-+IN)") (class "Default")
      (node (ref "C48") (pin "2") (pinfunction "2_2") (pintype "passive"))
      (node (ref "R63") (pin "2") (pinfunction "2_2") (pintype "passive"))
      (node (ref "U8") (pin "5") (pinfunction "+IN_5") (pintype "input"))
    )
    (net (code "116") (name "Net-(U8B--IN)") (class "Default")
      (node (ref "R61") (pin "2") (pinfunction "2_2") (pintype "passive"))
      (node (ref "R68") (pin "1") (pinfunction "1_1") (pintype "passive"))
      (node (ref "U8") (pin "6") (pinfunction "-IN_6") (pintype "input"))
    )
    (net (code "117") (name "Net-(U8B-OUT)") (class "Default")
      (node (ref "D3") (pin "A") (pinfunction "A_A") (pintype "passive"))
      (node (ref "U8") (pin "7") (pinfunction "OUT_7") (pintype "output"))
    )
    (net (code "118") (name "Net-(U9A--IN)") (class "Default")
      (node (ref "R64") (pin "1") (pinfunction "1_1") (pintype "passive"))
      (node (ref "R65") (pin "1") (pinfunction "1_1") (pintype "passive"))
      (node (ref "R66") (pin "1") (pinfunction "1_1") (pintype "passive"))
      (node (ref "R71") (pin "2") (pinfunction "2_2") (pintype "passive"))
      (node (ref "U9") (pin "2") (pinfunction "-IN_2") (pintype "input"))
    )
    (net (code "119") (name "Net-(U9A-OUT)") (class "Default")
      (node (ref "C54") (pin "1") (pinfunction "1_1") (pintype "passive"))
      (node (ref "R71") (pin "1") (pinfunction "1_1") (pintype "passive"))
      (node (ref "U9") (pin "1") (pinfunction "OUT_1") (pintype "output"))
    )
    (net (code "120") (name "Net-(U9B--IN)") (class "Default")
      (node (ref "R50") (pin "1") (pinfunction "1_1") (pintype "passive"))
      (node (ref "R54") (pin "2") (pinfunction "2_2") (pintype "passive"))
      (node (ref "U9") (pin "6") (pinfunction "-IN_6") (pintype "input"))
    )
    (net (code "121") (name "Net-(U9C--IN)") (class "Default")
      (node (ref "R51") (pin "1") (pinfunction "1_1") (pintype "passive"))
      (node (ref "R55") (pin "2") (pinfunction "2_2") (pintype "passive"))
      (node (ref "U9") (pin "9") (pinfunction "-IN_9") (pintype "input"))
    )
    (net (code "122") (name "Net-(U9D--IN)") (class "Default")
      (node (ref "R53") (pin "1") (pinfunction "1_1") (pintype "passive"))
      (node (ref "R56") (pin "2") (pinfunction "2_2") (pintype "passive"))
      (node (ref "U9") (pin "13") (pinfunction "-IN_13") (pintype "input"))
    )
    (net (code "123") (name "unconnected-(U2-NC-Pad4)") (class "Default")
      (node (ref "U2") (pin "4") (pinfunction "NC_4") (pintype "no_connect"))
    )
    (net (code "124") (name "unconnected-(U3-NC-Pad4)") (class "Default")
      (node (ref "U3") (pin "4") (pinfunction "NC_4") (pintype "no_connect"))
    )
    (net (code "125") (name "unconnected-(U4-NC-Pad4)") (class "Default")
      (node (ref "U4") (pin "4") (pinfunction "NC_4") (pintype "no_connect"))
    )
    (net (code "126") (name "unconnected-(U5-TA{slash}SDA-Pad13)") (class "Default")
      (node (ref "U5") (pin "13") (pinfunction "TA/SDA_13") (pintype "bidirectional"))
    )
    (net (code "127") (name "unconnected-(U7-NC-Pad13)") (class "Default")
      (node (ref "U7") (pin "13") (pinfunction "NC_13") (pintype "no_connect"))
    )
    (net (code "128") (name "unconnected-(U7-NC_2-Pad2)") (class "Default")
      (node (ref "U7") (pin "2") (pinfunction "NC_2_2") (pintype "no_connect"))
    )
  )
)
